# SwitchingRegulators.net
KiCad netlist of a schematic drawn in Altium Designer
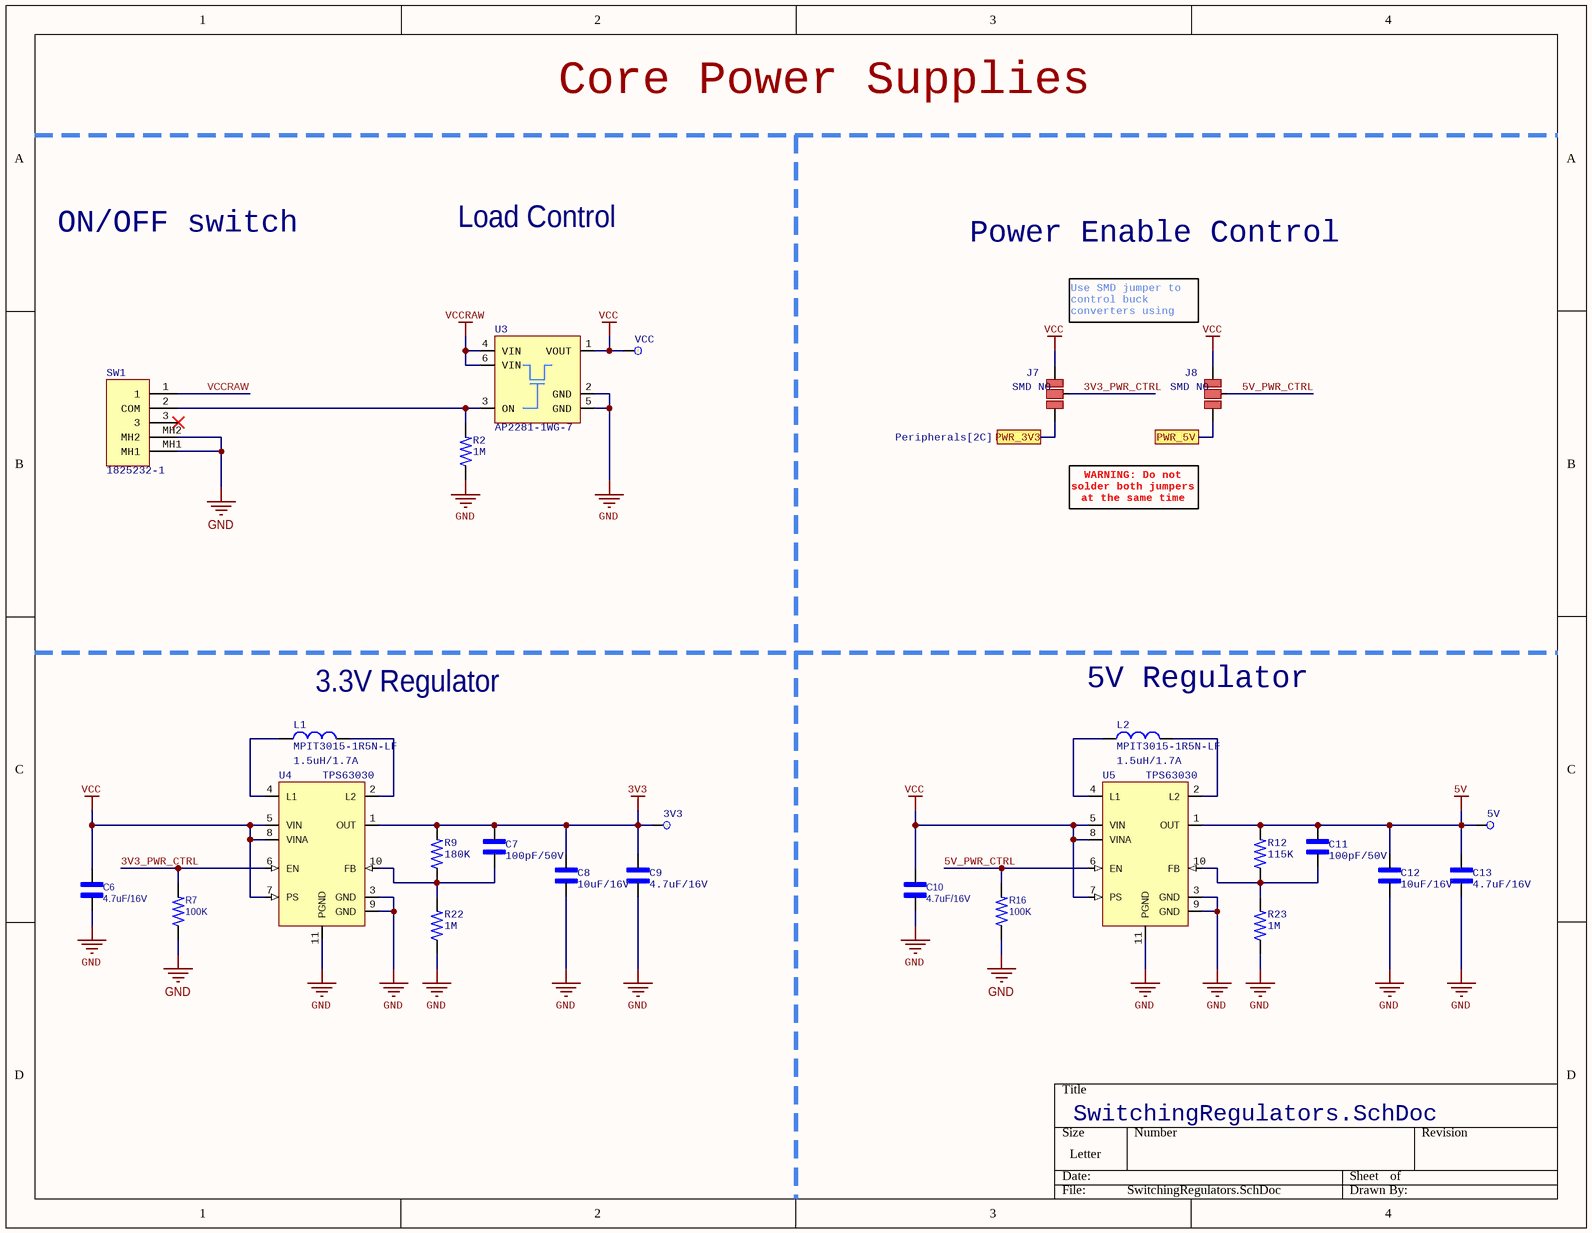
[diagram p0: SwitchingRegulators.SchDoc]

(export (version "E")
  (design (tool "Eeschema 10.0.6"))
  (components
    (comp (ref "3V3")
      (value "Test point 1.2mm")
      (footprint "TEST_POINT_1.2MM")
      (description "SMD test point")
      (libsource (lib "Connectors") (part "Test point"))
    )
    (comp (ref "5V")
      (value "Test point 1.2mm")
      (footprint "TEST_POINT_1.2MM")
      (description "SMD test point")
      (libsource (lib "Connectors") (part "Test point"))
    )
    (comp (ref "C6")
      (value "4.7uF/16V")
      (footprint "C0603")
      (description "MLCC 0603 4.7uF 16V 10% X5R")
      (fields (field (name "TOLERANCE") "10%"))
      (libsource (lib "Capacitors") (part "C0603 4.7uF/16V"))
    )
    (comp (ref "C7")
      (value "100pF/50V")
      (footprint "C0603")
      (fields
        (field (name "MANUFACTURER") "Kyocera AVX")
        (field (name "MANUFACTURER PART NUMBER") "06035A101JAT2A")
        (field (name "TOLERANCE") "5%")
      )
      (libsource (lib "Capacitors") (part "C0603 100pF/50V"))
    )
    (comp (ref "C8")
      (value "10uF/16V")
      (footprint "C0603")
      (description "MLCC 0603 10uF 16V 20% X5R")
      (fields (field (name "TOLERANCE") "20%"))
      (libsource (lib "Capacitors") (part "C0603 10uF/16V"))
    )
    (comp (ref "C9")
      (value "4.7uF/16V")
      (footprint "C0603")
      (description "MLCC 0603 4.7uF 16V 10% X5R")
      (fields (field (name "TOLERANCE") "10%"))
      (libsource (lib "Capacitors") (part "C0603 4.7uF/16V"))
    )
    (comp (ref "C10")
      (value "4.7uF/16V")
      (footprint "C0603")
      (description "MLCC 0603 4.7uF 16V 10% X5R")
      (fields (field (name "TOLERANCE") "10%"))
      (libsource (lib "Capacitors") (part "C0603 4.7uF/16V"))
    )
    (comp (ref "C11")
      (value "100pF/50V")
      (footprint "C0603")
      (fields
        (field (name "MANUFACTURER") "Kyocera AVX")
        (field (name "MANUFACTURER PART NUMBER") "06035A101JAT2A")
        (field (name "TOLERANCE") "5%")
      )
      (libsource (lib "Capacitors") (part "C0603 100pF/50V"))
    )
    (comp (ref "C12")
      (value "10uF/16V")
      (footprint "C0603")
      (description "MLCC 0603 10uF 16V 20% X5R")
      (fields (field (name "TOLERANCE") "20%"))
      (libsource (lib "Capacitors") (part "C0603 10uF/16V"))
    )
    (comp (ref "C13")
      (value "4.7uF/16V")
      (footprint "C0603")
      (description "MLCC 0603 4.7uF 16V 10% X5R")
      (fields (field (name "TOLERANCE") "10%"))
      (libsource (lib "Capacitors") (part "C0603 4.7uF/16V"))
    )
    (comp (ref "J7")
      (value "SMD NO")
      (footprint "JUMPER_SMD_NO_2WAY")
      (libsource (lib "Jumpers") (part "JUMPER_SMD_NO_2WAY"))
    )
    (comp (ref "J8")
      (value "SMD NO")
      (footprint "JUMPER_SMD_NO_2WAY")
      (libsource (lib "Jumpers") (part "JUMPER_SMD_NO_2WAY"))
    )
    (comp (ref "L1")
      (value "1.5uH/1.7A")
      (footprint "L3030_SHIELD_H15")
      (description "Inductor Power Shielded Wirewound 1.5uH 20% 152MHz Metal 2.3A 0.05Ohm DCR 1212 T/R")
      (fields (field (name "MANUFACTURER PART NUMBER 1") "MPIT3015-1R5N-LF"))
      (libsource (lib "Inductors") (part "MPIT3015-1R5N-LF"))
    )
    (comp (ref "L2")
      (value "1.5uH/1.7A")
      (footprint "L3030_SHIELD_H15")
      (description "Inductor Power Shielded Wirewound 1.5uH 20% 152MHz Metal 2.3A 0.05Ohm DCR 1212 T/R")
      (fields (field (name "MANUFACTURER PART NUMBER 1") "MPIT3015-1R5N-LF"))
      (libsource (lib "Inductors") (part "MPIT3015-1R5N-LF"))
    )
    (comp (ref "R2")
      (value "1M")
      (footprint "R0603")
      (description "RES SMD 1M OHM 1% 1/10W 0603")
      (fields
        (field (name "MANUFACTURER") "Yageo")
        (field (name "MANUFACTURER PART NUMBER") "RC0603FR-071ML")
      )
      (libsource (lib "Resistors") (part "R0603 1M"))
    )
    (comp (ref "R7")
      (value "100K")
      (footprint "R0603")
      (description "RES 0603 100K OHM 1% 1/10W")
      (fields
        (field (name "MANUFACTURER") "Yageo")
        (field (name "MANUFACTURER PART NUMBER") "RC0603FR-07100KL")
      )
      (libsource (lib "Resistors") (part "R0603 100K"))
    )
    (comp (ref "R9")
      (value "180K")
      (footprint "R0603")
      (description "RES 0603 220K OHM 1% 1/10W")
      (fields (field (name "TOLERANCE") "1%"))
      (libsource (lib "Resistors") (part "R0603 220K"))
    )
    (comp (ref "R12")
      (value "115K")
      (footprint "R0603")
      (description "RES 0603 115K OHM 1% 1/10W")
      (fields (field (name "TOLERANCE") "1%"))
      (libsource (lib "Resistors") (part "R0603 220K"))
    )
    (comp (ref "R16")
      (value "100K")
      (footprint "R0603")
      (description "RES 0603 100K OHM 1% 1/10W")
      (fields
        (field (name "MANUFACTURER") "Yageo")
        (field (name "MANUFACTURER PART NUMBER") "RC0603FR-07100KL")
      )
      (libsource (lib "Resistors") (part "R0603 100K"))
    )
    (comp (ref "R22")
      (value "1M")
      (footprint "R0603")
      (description "RES 0603 1M OHM 1% 1/10W")
      (fields (field (name "TOLERANCE") "1%"))
      (libsource (lib "Resistors") (part "R0603 1M"))
    )
    (comp (ref "R23")
      (value "1M")
      (footprint "R0603")
      (description "RES 0603 2M OHM 1% 1/10W")
      (libsource (lib "Resistors") (part "R0603 2M"))
    )
    (comp (ref "SW1")
      (value "1825232-1")
      (footprint "1825232-1")
      (description "Slide Switch, SPDT, On-on, Latched, 0.2A, 30VDC, Solder Terminal, Panel Mount")
      (fields (field (name "MANUFACTURER") "TE Connectivity AMP"))
      (libsource (lib "Switches") (part "1825232-1"))
    )
    (comp (ref "U3")
      (value "AP2281-1WG-7")
      (footprint "SOT-26-6")
      (description "Load Switch P-Channel 2A SOT-26-6")
      (fields (field (name "MANUFACTURER") "Diodes"))
      (libsource (lib "IC Power") (part "AP2281-1WG-7"))
    )
    (comp (ref "U4")
      (value "TPS63030")
      (footprint "WSON-N10")
      (libsource (lib "IC Power") (part "TPS63030DSKR"))
    )
    (comp (ref "U5")
      (value "TPS63030")
      (footprint "WSON-N10")
      (libsource (lib "IC Power") (part "TPS63030DSKR"))
    )
    (comp (ref "VCC")
      (value "Test point 1.2mm")
      (footprint "TEST_POINT_1.2MM")
      (description "SMD test point")
      (libsource (lib "Connectors") (part "Test point"))
    )
  )
  (nets
    (net (code "1") (name "/3V3_PWR_CTRL") (class "Default")
      (node (ref "J7") (pin "2") (pinfunction "2_2") (pintype "passive"))
      (node (ref "R7") (pin "2") (pinfunction "2_2") (pintype "passive"))
      (node (ref "U4") (pin "6") (pinfunction "EN_6") (pintype "input"))
    )
    (net (code "2") (name "/5V_PWR_CTRL") (class "Default")
      (node (ref "J8") (pin "2") (pinfunction "2_2") (pintype "passive"))
      (node (ref "R16") (pin "2") (pinfunction "2_2") (pintype "passive"))
      (node (ref "U5") (pin "6") (pinfunction "EN_6") (pintype "input"))
    )
    (net (code "3") (name "/PWR_3V3") (class "Default")
      (node (ref "J7") (pin "1") (pinfunction "1_1") (pintype "passive"))
    )
    (net (code "4") (name "/PWR_5V") (class "Default")
      (node (ref "J8") (pin "1") (pinfunction "1_1") (pintype "passive"))
    )
    (net (code "5") (name "3V3") (class "Default")
      (node (ref "3V3") (pin "1") (pinfunction "1_1") (pintype "passive"))
      (node (ref "C7") (pin "1") (pinfunction "1_1") (pintype "passive"))
      (node (ref "C8") (pin "1") (pinfunction "1_1") (pintype "passive"))
      (node (ref "C9") (pin "1") (pinfunction "1_1") (pintype "passive"))
      (node (ref "R9") (pin "2") (pinfunction "2_2") (pintype "passive"))
      (node (ref "U4") (pin "1") (pinfunction "OUT_1") (pintype "power_in"))
    )
    (net (code "6") (name "5V") (class "Default")
      (node (ref "5V") (pin "1") (pinfunction "1_1") (pintype "passive"))
      (node (ref "C11") (pin "1") (pinfunction "1_1") (pintype "passive"))
      (node (ref "C12") (pin "1") (pinfunction "1_1") (pintype "passive"))
      (node (ref "C13") (pin "1") (pinfunction "1_1") (pintype "passive"))
      (node (ref "R12") (pin "2") (pinfunction "2_2") (pintype "passive"))
      (node (ref "U5") (pin "1") (pinfunction "OUT_1") (pintype "power_in"))
    )
    (net (code "7") (name "GND") (class "Default")
      (node (ref "C10") (pin "2") (pinfunction "2_2") (pintype "passive"))
      (node (ref "C12") (pin "2") (pinfunction "2_2") (pintype "passive"))
      (node (ref "C13") (pin "2") (pinfunction "2_2") (pintype "passive"))
      (node (ref "C6") (pin "2") (pinfunction "2_2") (pintype "passive"))
      (node (ref "C8") (pin "2") (pinfunction "2_2") (pintype "passive"))
      (node (ref "C9") (pin "2") (pinfunction "2_2") (pintype "passive"))
      (node (ref "R16") (pin "1") (pinfunction "1_1") (pintype "passive"))
      (node (ref "R2") (pin "1") (pinfunction "1_1") (pintype "passive"))
      (node (ref "R22") (pin "1") (pinfunction "1_1") (pintype "passive"))
      (node (ref "R23") (pin "1") (pinfunction "1_1") (pintype "passive"))
      (node (ref "R7") (pin "1") (pinfunction "1_1") (pintype "passive"))
      (node (ref "SW1") (pin "MH1") (pinfunction "MH1_MH1") (pintype "passive"))
      (node (ref "SW1") (pin "MH2") (pinfunction "MH2_MH2") (pintype "passive"))
      (node (ref "U3") (pin "2") (pinfunction "GND_2") (pintype "passive"))
      (node (ref "U3") (pin "5") (pinfunction "GND_5") (pintype "passive"))
      (node (ref "U4") (pin "11") (pinfunction "PGND_11") (pintype "power_in"))
      (node (ref "U4") (pin "3") (pinfunction "GND_3") (pintype "power_in"))
      (node (ref "U4") (pin "9") (pinfunction "GND_9") (pintype "power_in"))
      (node (ref "U5") (pin "11") (pinfunction "PGND_11") (pintype "power_in"))
      (node (ref "U5") (pin "3") (pinfunction "GND_3") (pintype "power_in"))
      (node (ref "U5") (pin "9") (pinfunction "GND_9") (pintype "power_in"))
    )
    (net (code "8") (name "Net-(SW1-COM)") (class "Default")
      (node (ref "R2") (pin "2") (pinfunction "2_2") (pintype "passive"))
      (node (ref "SW1") (pin "2") (pinfunction "COM_2") (pintype "passive"))
      (node (ref "U3") (pin "3") (pinfunction "ON_3") (pintype "passive"))
    )
    (net (code "9") (name "Net-(U4-FB)") (class "Default")
      (node (ref "C7") (pin "2") (pinfunction "2_2") (pintype "passive"))
      (node (ref "R22") (pin "2") (pinfunction "2_2") (pintype "passive"))
      (node (ref "R9") (pin "1") (pinfunction "1_1") (pintype "passive"))
      (node (ref "U4") (pin "10") (pinfunction "FB_10") (pintype "input"))
    )
    (net (code "10") (name "Net-(U4-L1)") (class "Default")
      (node (ref "L1") (pin "1") (pinfunction "1_1") (pintype "passive"))
      (node (ref "U4") (pin "4") (pinfunction "L1_4") (pintype "passive"))
    )
    (net (code "11") (name "Net-(U4-L2)") (class "Default")
      (node (ref "L1") (pin "2") (pinfunction "2_2") (pintype "passive"))
      (node (ref "U4") (pin "2") (pinfunction "L2_2") (pintype "passive"))
    )
    (net (code "12") (name "Net-(U5-FB)") (class "Default")
      (node (ref "C11") (pin "2") (pinfunction "2_2") (pintype "passive"))
      (node (ref "R12") (pin "1") (pinfunction "1_1") (pintype "passive"))
      (node (ref "R23") (pin "2") (pinfunction "2_2") (pintype "passive"))
      (node (ref "U5") (pin "10") (pinfunction "FB_10") (pintype "input"))
    )
    (net (code "13") (name "Net-(U5-L1)") (class "Default")
      (node (ref "L2") (pin "1") (pinfunction "1_1") (pintype "passive"))
      (node (ref "U5") (pin "4") (pinfunction "L1_4") (pintype "passive"))
    )
    (net (code "14") (name "Net-(U5-L2)") (class "Default")
      (node (ref "L2") (pin "2") (pinfunction "2_2") (pintype "passive"))
      (node (ref "U5") (pin "2") (pinfunction "L2_2") (pintype "passive"))
    )
    (net (code "15") (name "VCC") (class "Default")
      (node (ref "C10") (pin "1") (pinfunction "1_1") (pintype "passive"))
      (node (ref "C6") (pin "1") (pinfunction "1_1") (pintype "passive"))
      (node (ref "J7") (pin "3") (pinfunction "3_3") (pintype "passive"))
      (node (ref "J8") (pin "3") (pinfunction "3_3") (pintype "passive"))
      (node (ref "U3") (pin "1") (pinfunction "VOUT_1") (pintype "passive"))
      (node (ref "U4") (pin "5") (pinfunction "VIN_5") (pintype "power_in"))
      (node (ref "U4") (pin "7") (pinfunction "PS_7") (pintype "input"))
      (node (ref "U4") (pin "8") (pinfunction "VINA_8") (pintype "power_in"))
      (node (ref "U5") (pin "5") (pinfunction "VIN_5") (pintype "power_in"))
      (node (ref "U5") (pin "7") (pinfunction "PS_7") (pintype "input"))
      (node (ref "U5") (pin "8") (pinfunction "VINA_8") (pintype "power_in"))
      (node (ref "VCC") (pin "1") (pinfunction "1_1") (pintype "passive"))
    )
    (net (code "16") (name "VCCRAW") (class "Default")
      (node (ref "SW1") (pin "1") (pinfunction "1_1") (pintype "passive"))
      (node (ref "U3") (pin "4") (pinfunction "VIN_4") (pintype "passive"))
      (node (ref "U3") (pin "6") (pinfunction "VIN_6") (pintype "passive"))
    )
    (net (code "17") (name "unconnected-(SW1-Pad3)") (class "Default")
      (node (ref "SW1") (pin "3") (pinfunction "3_3") (pintype "passive+no_connect"))
    )
  )
)
